# Sheet_1.net
KiCad netlist of a schematic drawn in Altium Designer
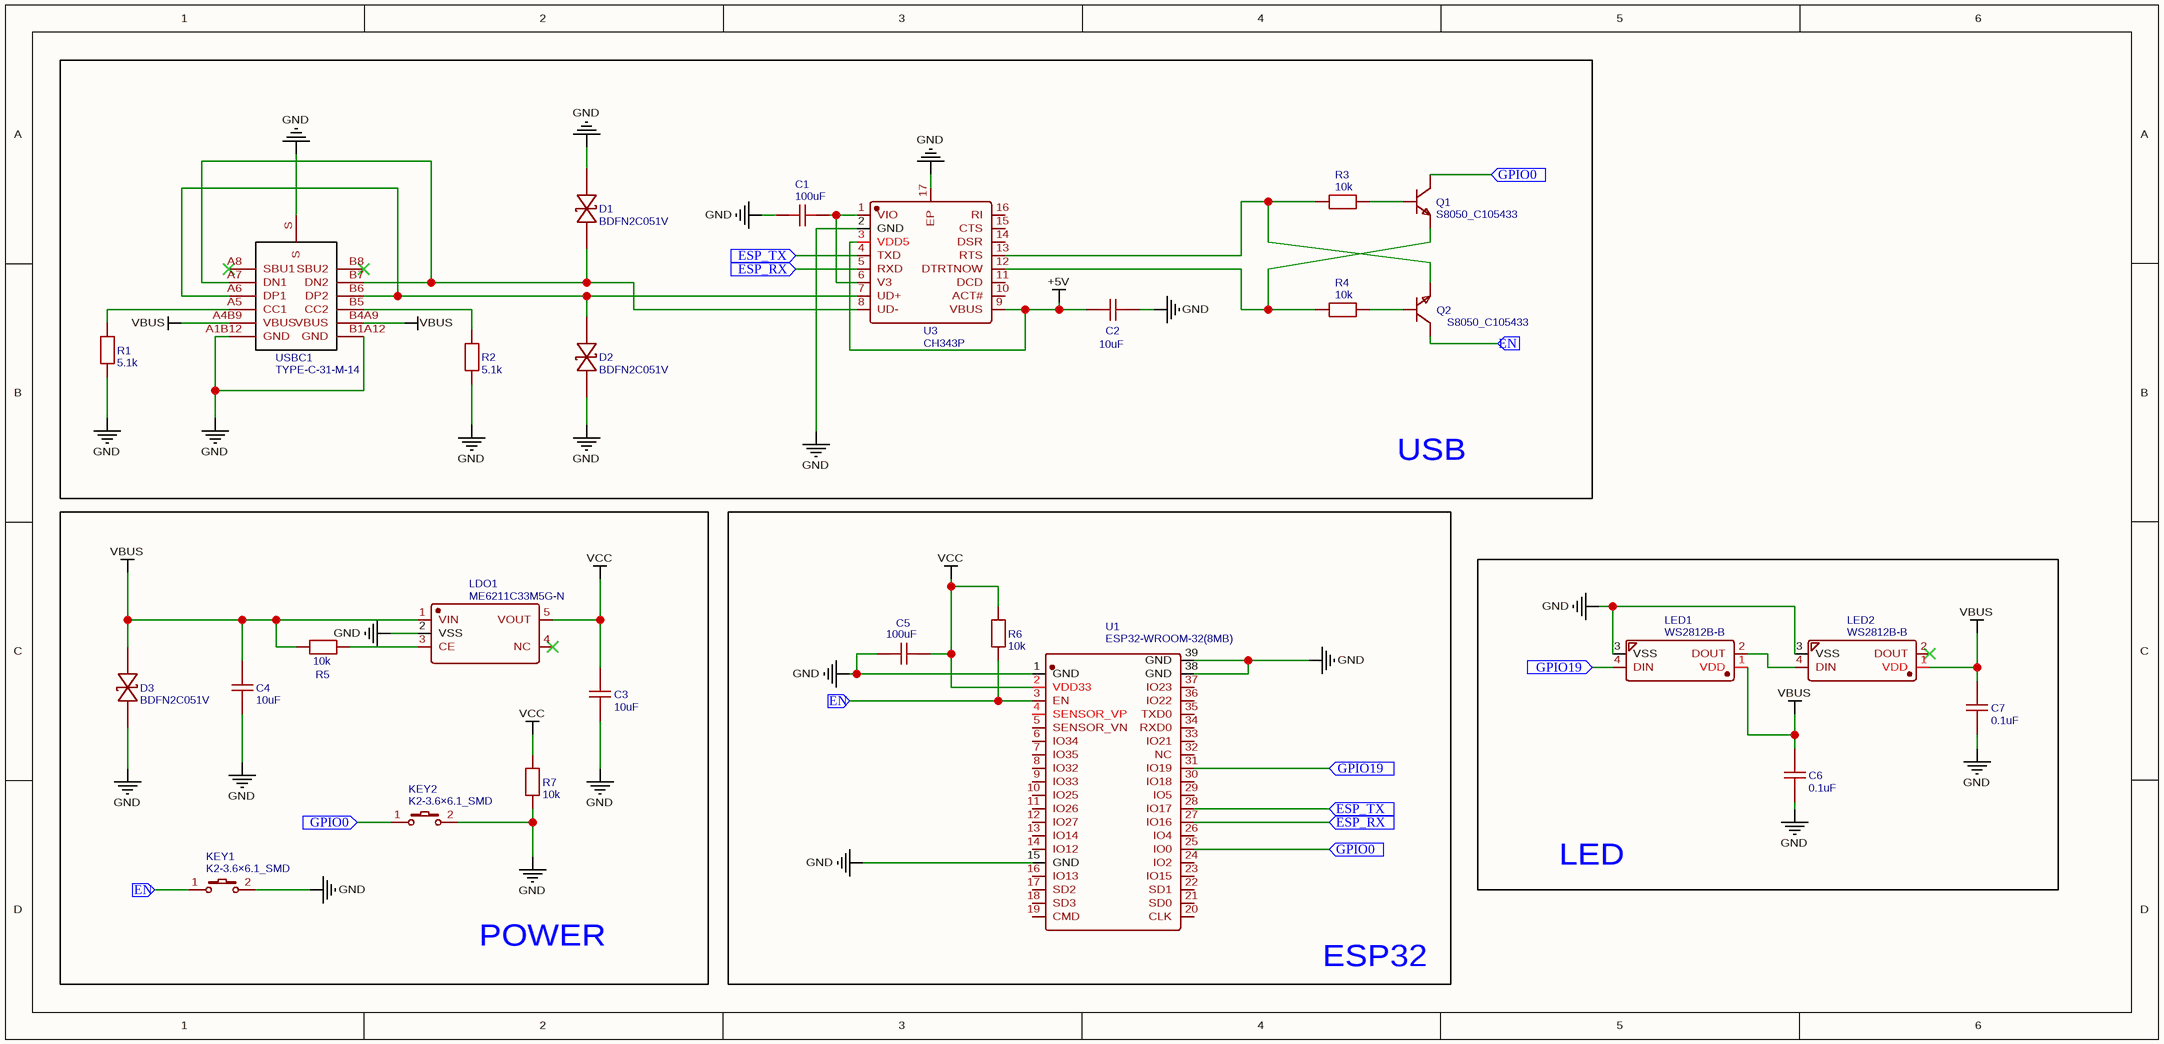
[diagram p0: Sheet_1.schdoc]

(export (version "E")
  (design (tool "Eeschema 10.0.6"))
  (components
    (comp (ref "C1")
      (value "100uF")
      (fields (field (name "CONTRIBUTOR") "LCEDA_Lib"))
      (libsource (lib "altium-import") (part "root_0_100uF_"))
    )
    (comp (ref "C2")
      (value "10uF")
      (fields (field (name "CONTRIBUTOR") "LCEDA_Lib"))
      (libsource (lib "altium-import") (part "root_0_10uF_"))
    )
    (comp (ref "C3")
      (value "10uF")
      (fields (field (name "CONTRIBUTOR") "LCEDA_Lib"))
      (libsource (lib "altium-import") (part "root_1_10uF_"))
    )
    (comp (ref "C4")
      (value "10uF")
      (fields (field (name "CONTRIBUTOR") "LCEDA_Lib"))
      (libsource (lib "altium-import") (part "root_1_10uF_"))
    )
    (comp (ref "C5")
      (value "100uF")
      (fields (field (name "CONTRIBUTOR") "LCEDA_Lib"))
      (libsource (lib "altium-import") (part "root_0_100uF_"))
    )
    (comp (ref "C6")
      (value "0.1uF")
      (fields (field (name "CONTRIBUTOR") "LCEDA_Lib"))
      (libsource (lib "altium-import") (part "root_3_0.1uF_"))
    )
    (comp (ref "C7")
      (value "0.1uF")
      (fields (field (name "CONTRIBUTOR") "LCEDA_Lib"))
      (libsource (lib "altium-import") (part "root_3_0.1uF_"))
    )
    (comp (ref "D1")
      (value "BDFN2C051V")
      (fields (field (name "BOM_SUPPLIER PART") "C152024") (field (name "CONTRIBUTOR") "LCSC"))
      (libsource (lib "altium-import") (part "root_3_BDFN2C051V_"))
    )
    (comp (ref "D2")
      (value "BDFN2C051V")
      (fields (field (name "BOM_SUPPLIER PART") "C152024") (field (name "CONTRIBUTOR") "LCSC"))
      (libsource (lib "altium-import") (part "root_3_BDFN2C051V_"))
    )
    (comp (ref "D3")
      (value "BDFN2C051V")
      (fields (field (name "BOM_SUPPLIER PART") "C152024") (field (name "CONTRIBUTOR") "LCSC"))
      (libsource (lib "altium-import") (part "root_3_BDFN2C051V_"))
    )
    (comp (ref "KEY1")
      (value "K2-3.6×6.1_SMD")
      (fields
        (field (name "BOM_SUPPLIER PART") "C118141")
        (field (name "BOM_MANUFACTURER PART") "K2-1107ST-A4SW-06")
        (field (name "CONTRIBUTOR") "LCEDA_Lib")
      )
      (libsource (lib "altium-import") (part "root_0_K2-3.6×6.1_SMD_"))
    )
    (comp (ref "KEY2")
      (value "K2-3.6×6.1_SMD")
      (fields
        (field (name "BOM_SUPPLIER PART") "C118141")
        (field (name "BOM_MANUFACTURER PART") "K2-1107ST-A4SW-06")
        (field (name "CONTRIBUTOR") "LCEDA_Lib")
      )
      (libsource (lib "altium-import") (part "root_0_K2-3.6×6.1_SMD_"))
    )
    (comp (ref "LDO1")
      (value "ME6211C33M5G-N")
      (fields (field (name "BOM_SUPPLIER PART") "C82942"))
      (libsource (lib "altium-import") (part "root_0_ME6211C33M5G-N_"))
    )
    (comp (ref "LED1")
      (value "WS2812B-B")
      (fields (field (name "BOM_SUPPLIER PART") "C114586") (field (name "CONTRIBUTOR") "LCSC"))
      (libsource (lib "altium-import") (part "root_2_WS2812B-B_"))
    )
    (comp (ref "LED2")
      (value "WS2812B-B")
      (fields (field (name "BOM_SUPPLIER PART") "C114586") (field (name "CONTRIBUTOR") "LCSC"))
      (libsource (lib "altium-import") (part "root_2_WS2812B-B_"))
    )
    (comp (ref "Q1")
      (value "S8050_C105433")
      (fields (field (name "BOM_MANUFACTURER PART") "S8050") (field (name "BOM_SUPPLIER PART") "C105433"))
      (libsource (lib "altium-import") (part "root_0_S8050_C105433_"))
    )
    (comp (ref "Q2")
      (value "S8050_C105433")
      (fields (field (name "BOM_MANUFACTURER PART") "S8050") (field (name "BOM_SUPPLIER PART") "C105433"))
      (libsource (lib "altium-import") (part "root_2_S8050_C105433_"))
    )
    (comp (ref "R1")
      (value "5.1k")
      (fields (field (name "CONTRIBUTOR") "LCEDA_Lib"))
      (libsource (lib "altium-import") (part "root_3_5.1k_"))
    )
    (comp (ref "R2")
      (value "5.1k")
      (fields (field (name "CONTRIBUTOR") "LCEDA_Lib"))
      (libsource (lib "altium-import") (part "root_3_5.1k_"))
    )
    (comp (ref "R3")
      (value "10k")
      (fields (field (name "CONTRIBUTOR") "LCEDA_Lib"))
      (libsource (lib "altium-import") (part "root_0_10k_"))
    )
    (comp (ref "R4")
      (value "10k")
      (fields (field (name "CONTRIBUTOR") "LCEDA_Lib"))
      (libsource (lib "altium-import") (part "root_0_10k_"))
    )
    (comp (ref "R5")
      (value "10k")
      (fields (field (name "CONTRIBUTOR") "LCEDA_Lib"))
      (libsource (lib "altium-import") (part "root_0_10k_"))
    )
    (comp (ref "R6")
      (value "10k")
      (fields (field (name "CONTRIBUTOR") "LCEDA_Lib"))
      (libsource (lib "altium-import") (part "root_1_10k_"))
    )
    (comp (ref "R7")
      (value "10k")
      (fields (field (name "CONTRIBUTOR") "LCEDA_Lib"))
      (libsource (lib "altium-import") (part "root_1_10k_"))
    )
    (comp (ref "U1")
      (value "ESP32-WROOM-32(8MB)")
      (fields
        (field (name "BOM_SUPPLIER PART") "C529582")
        (field (name "BOM_MANUFACTURER PART") "ESP32-WROOM-32-N8")
        (field (name "CONTRIBUTOR") "LCSC")
      )
      (libsource (lib "altium-import") (part "root_0_ESP32-WROOM-32(8MB)_"))
    )
    (comp (ref "U3")
      (value "CH343P")
      (fields (field (name "BOM_SUPPLIER PART") "C2846043") (field (name "CONTRIBUTOR") "LCSC"))
      (libsource (lib "altium-import") (part "root_0_CH343P_"))
    )
    (comp (ref "USBC1")
      (value "TYPE-C-31-M-14")
      (fields (field (name "BOM_SUPPLIER PART") "C223907") (field (name "CONTRIBUTOR") "LCSC"))
      (libsource (lib "altium-import") (part "root_1_TYPE-C-31-M-14_"))
    )
  )
  (nets
    (net (code "1") (name "+5V") (class "Default")
      (node (ref "C2") (pin "1") (pinfunction "1_1") (pintype "passive"))
      (node (ref "U3") (pin "3") (pinfunction "VDD5_3") (pintype "passive"))
      (node (ref "U3") (pin "9") (pinfunction "VBUS_9") (pintype "passive"))
    )
    (net (code "2") (name "/EN") (class "Default")
      (node (ref "KEY1") (pin "1") (pinfunction "1_1") (pintype "passive"))
      (node (ref "Q2") (pin "3") (pinfunction "3_3") (pintype "passive"))
      (node (ref "R6") (pin "1") (pinfunction "1_1") (pintype "passive"))
      (node (ref "U1") (pin "3") (pinfunction "EN_3") (pintype "passive"))
    )
    (net (code "3") (name "/ESP_RX") (class "Default")
      (node (ref "U1") (pin "27") (pinfunction "IO16_27") (pintype "passive"))
      (node (ref "U3") (pin "5") (pinfunction "RXD_5") (pintype "passive"))
    )
    (net (code "4") (name "/ESP_TX") (class "Default")
      (node (ref "U1") (pin "28") (pinfunction "IO17_28") (pintype "passive"))
      (node (ref "U3") (pin "4") (pinfunction "TXD_4") (pintype "passive"))
    )
    (net (code "5") (name "/GPIO0") (class "Default")
      (node (ref "KEY2") (pin "1") (pinfunction "1_1") (pintype "passive"))
      (node (ref "Q1") (pin "3") (pinfunction "3_3") (pintype "passive"))
      (node (ref "U1") (pin "25") (pinfunction "IO0_25") (pintype "passive"))
    )
    (net (code "6") (name "/GPIO19") (class "Default")
      (node (ref "LED1") (pin "4") (pinfunction "DIN_4") (pintype "passive"))
      (node (ref "U1") (pin "31") (pinfunction "IO19_31") (pintype "passive"))
    )
    (net (code "7") (name "GND") (class "Default")
      (node (ref "C1") (pin "1") (pinfunction "1_1") (pintype "passive"))
      (node (ref "C2") (pin "2") (pinfunction "2_2") (pintype "passive"))
      (node (ref "C3") (pin "1") (pinfunction "1_1") (pintype "passive"))
      (node (ref "C4") (pin "1") (pinfunction "1_1") (pintype "passive"))
      (node (ref "C5") (pin "1") (pinfunction "1_1") (pintype "passive"))
      (node (ref "C6") (pin "2") (pinfunction "2_2") (pintype "passive"))
      (node (ref "C7") (pin "2") (pinfunction "2_2") (pintype "passive"))
      (node (ref "D1") (pin "1") (pinfunction "1_1") (pintype "passive"))
      (node (ref "D2") (pin "2") (pinfunction "2_2") (pintype "passive"))
      (node (ref "D3") (pin "2") (pinfunction "2_2") (pintype "passive"))
      (node (ref "KEY1") (pin "2") (pinfunction "2_2") (pintype "passive"))
      (node (ref "KEY2") (pin "2") (pinfunction "2_2") (pintype "passive"))
      (node (ref "LDO1") (pin "2") (pinfunction "VSS_2") (pintype "passive"))
      (node (ref "LED1") (pin "3") (pinfunction "VSS_3") (pintype "passive"))
      (node (ref "LED2") (pin "3") (pinfunction "VSS_3") (pintype "passive"))
      (node (ref "R1") (pin "2") (pinfunction "2_2") (pintype "passive"))
      (node (ref "R2") (pin "2") (pinfunction "2_2") (pintype "passive"))
      (node (ref "R7") (pin "1") (pinfunction "1_1") (pintype "passive"))
      (node (ref "U1") (pin "1") (pinfunction "GND_1") (pintype "passive"))
      (node (ref "U1") (pin "15") (pinfunction "GND_15") (pintype "passive"))
      (node (ref "U1") (pin "38") (pinfunction "GND_38") (pintype "passive"))
      (node (ref "U1") (pin "39") (pinfunction "GND_39") (pintype "passive"))
      (node (ref "U3") (pin "17") (pinfunction "EP_17") (pintype "passive"))
      (node (ref "U3") (pin "2") (pinfunction "GND_2") (pintype "passive"))
      (node (ref "USBC1") (pin "A1B12") (pinfunction "GND_A1B12") (pintype "passive"))
      (node (ref "USBC1") (pin "B1A12") (pinfunction "GND_B1A12") (pintype "passive"))
      (node (ref "USBC1") (pin "S") (pinfunction "S_S") (pintype "passive"))
    )
    (net (code "8") (name "Net-(LDO1-CE)") (class "Default")
      (node (ref "LDO1") (pin "3") (pinfunction "CE_3") (pintype "passive"))
      (node (ref "R5") (pin "2") (pinfunction "2_2") (pintype "passive"))
    )
    (net (code "9") (name "Net-(LED1-DOUT)") (class "Default")
      (node (ref "LED1") (pin "2") (pinfunction "DOUT_2") (pintype "passive"))
      (node (ref "LED2") (pin "4") (pinfunction "DIN_4") (pintype "passive"))
    )
    (net (code "10") (name "Net-(Q1-Pad1)") (class "Default")
      (node (ref "Q1") (pin "1") (pinfunction "1_1") (pintype "passive"))
      (node (ref "R3") (pin "2") (pinfunction "2_2") (pintype "passive"))
    )
    (net (code "11") (name "Net-(Q2-Pad1)") (class "Default")
      (node (ref "Q2") (pin "1") (pinfunction "1_1") (pintype "passive"))
      (node (ref "R4") (pin "2") (pinfunction "2_2") (pintype "passive"))
    )
    (net (code "12") (name "Net-(U3-DTRTNOW)") (class "Default")
      (node (ref "Q1") (pin "2") (pinfunction "2_2") (pintype "passive"))
      (node (ref "R4") (pin "1") (pinfunction "1_1") (pintype "passive"))
      (node (ref "U3") (pin "12") (pinfunction "DTRTNOW_12") (pintype "passive"))
    )
    (net (code "13") (name "Net-(U3-RTS)") (class "Default")
      (node (ref "Q2") (pin "2") (pinfunction "2_2") (pintype "passive"))
      (node (ref "R3") (pin "1") (pinfunction "1_1") (pintype "passive"))
      (node (ref "U3") (pin "13") (pinfunction "RTS_13") (pintype "passive"))
    )
    (net (code "14") (name "Net-(U3-UD+)") (class "Default")
      (node (ref "D2") (pin "1") (pinfunction "1_1") (pintype "passive"))
      (node (ref "U3") (pin "7") (pinfunction "UD+_7") (pintype "passive"))
      (node (ref "USBC1") (pin "A6") (pinfunction "DP1_A6") (pintype "passive"))
      (node (ref "USBC1") (pin "B6") (pinfunction "DP2_B6") (pintype "passive"))
    )
    (net (code "15") (name "Net-(U3-UD-)") (class "Default")
      (node (ref "D1") (pin "2") (pinfunction "2_2") (pintype "passive"))
      (node (ref "U3") (pin "8") (pinfunction "UD-_8") (pintype "passive"))
      (node (ref "USBC1") (pin "A7") (pinfunction "DN1_A7") (pintype "passive"))
      (node (ref "USBC1") (pin "B7") (pinfunction "DN2_B7") (pintype "passive"))
    )
    (net (code "16") (name "Net-(U3-V3)") (class "Default")
      (node (ref "C1") (pin "2") (pinfunction "2_2") (pintype "passive"))
      (node (ref "U3") (pin "1") (pinfunction "VIO_1") (pintype "passive"))
      (node (ref "U3") (pin "6") (pinfunction "V3_6") (pintype "passive"))
    )
    (net (code "17") (name "Net-(USBC1-CC1)") (class "Default")
      (node (ref "R1") (pin "1") (pinfunction "1_1") (pintype "passive"))
      (node (ref "USBC1") (pin "A5") (pinfunction "CC1_A5") (pintype "passive"))
    )
    (net (code "18") (name "Net-(USBC1-CC2)") (class "Default")
      (node (ref "R2") (pin "1") (pinfunction "1_1") (pintype "passive"))
      (node (ref "USBC1") (pin "B5") (pinfunction "CC2_B5") (pintype "passive"))
    )
    (net (code "19") (name "VBUS") (class "Default")
      (node (ref "C4") (pin "2") (pinfunction "2_2") (pintype "passive"))
      (node (ref "C6") (pin "1") (pinfunction "1_1") (pintype "passive"))
      (node (ref "C7") (pin "1") (pinfunction "1_1") (pintype "passive"))
      (node (ref "D3") (pin "1") (pinfunction "1_1") (pintype "passive"))
      (node (ref "LDO1") (pin "1") (pinfunction "VIN_1") (pintype "passive"))
      (node (ref "LED1") (pin "1") (pinfunction "VDD_1") (pintype "passive"))
      (node (ref "LED2") (pin "1") (pinfunction "VDD_1") (pintype "passive"))
      (node (ref "R5") (pin "1") (pinfunction "1_1") (pintype "passive"))
      (node (ref "USBC1") (pin "A4B9") (pinfunction "VBUS_A4B9") (pintype "passive"))
      (node (ref "USBC1") (pin "B4A9") (pinfunction "VBUS_B4A9") (pintype "passive"))
    )
    (net (code "20") (name "VCC") (class "Default")
      (node (ref "C3") (pin "2") (pinfunction "2_2") (pintype "passive"))
      (node (ref "C5") (pin "2") (pinfunction "2_2") (pintype "passive"))
      (node (ref "LDO1") (pin "5") (pinfunction "VOUT_5") (pintype "passive"))
      (node (ref "R6") (pin "2") (pinfunction "2_2") (pintype "passive"))
      (node (ref "R7") (pin "2") (pinfunction "2_2") (pintype "passive"))
      (node (ref "U1") (pin "2") (pinfunction "VDD33_2") (pintype "passive"))
    )
    (net (code "21") (name "unconnected-(LDO1-NC-Pad4)") (class "Default")
      (node (ref "LDO1") (pin "4") (pinfunction "NC_4") (pintype "passive+no_connect"))
    )
    (net (code "22") (name "unconnected-(LED2-DOUT-Pad2)") (class "Default")
      (node (ref "LED2") (pin "2") (pinfunction "DOUT_2") (pintype "passive+no_connect"))
    )
    (net (code "23") (name "unconnected-(U1-CLK-Pad20)") (class "Default")
      (node (ref "U1") (pin "20") (pinfunction "CLK_20") (pintype "passive"))
    )
    (net (code "24") (name "unconnected-(U1-CMD-Pad19)") (class "Default")
      (node (ref "U1") (pin "19") (pinfunction "CMD_19") (pintype "passive"))
    )
    (net (code "25") (name "unconnected-(U1-IO2-Pad24)") (class "Default")
      (node (ref "U1") (pin "24") (pinfunction "IO2_24") (pintype "passive"))
    )
    (net (code "26") (name "unconnected-(U1-IO4-Pad26)") (class "Default")
      (node (ref "U1") (pin "26") (pinfunction "IO4_26") (pintype "passive"))
    )
    (net (code "27") (name "unconnected-(U1-IO5-Pad29)") (class "Default")
      (node (ref "U1") (pin "29") (pinfunction "IO5_29") (pintype "passive"))
    )
    (net (code "28") (name "unconnected-(U1-IO12-Pad14)") (class "Default")
      (node (ref "U1") (pin "14") (pinfunction "IO12_14") (pintype "passive"))
    )
    (net (code "29") (name "unconnected-(U1-IO13-Pad16)") (class "Default")
      (node (ref "U1") (pin "16") (pinfunction "IO13_16") (pintype "passive"))
    )
    (net (code "30") (name "unconnected-(U1-IO14-Pad13)") (class "Default")
      (node (ref "U1") (pin "13") (pinfunction "IO14_13") (pintype "passive"))
    )
    (net (code "31") (name "unconnected-(U1-IO15-Pad23)") (class "Default")
      (node (ref "U1") (pin "23") (pinfunction "IO15_23") (pintype "passive"))
    )
    (net (code "32") (name "unconnected-(U1-IO18-Pad30)") (class "Default")
      (node (ref "U1") (pin "30") (pinfunction "IO18_30") (pintype "passive"))
    )
    (net (code "33") (name "unconnected-(U1-IO21-Pad33)") (class "Default")
      (node (ref "U1") (pin "33") (pinfunction "IO21_33") (pintype "passive"))
    )
    (net (code "34") (name "unconnected-(U1-IO22-Pad36)") (class "Default")
      (node (ref "U1") (pin "36") (pinfunction "IO22_36") (pintype "passive"))
    )
    (net (code "35") (name "unconnected-(U1-IO23-Pad37)") (class "Default")
      (node (ref "U1") (pin "37") (pinfunction "IO23_37") (pintype "passive"))
    )
    (net (code "36") (name "unconnected-(U1-IO25-Pad10)") (class "Default")
      (node (ref "U1") (pin "10") (pinfunction "IO25_10") (pintype "passive"))
    )
    (net (code "37") (name "unconnected-(U1-IO26-Pad11)") (class "Default")
      (node (ref "U1") (pin "11") (pinfunction "IO26_11") (pintype "passive"))
    )
    (net (code "38") (name "unconnected-(U1-IO27-Pad12)") (class "Default")
      (node (ref "U1") (pin "12") (pinfunction "IO27_12") (pintype "passive"))
    )
    (net (code "39") (name "unconnected-(U1-IO32-Pad8)") (class "Default")
      (node (ref "U1") (pin "8") (pinfunction "IO32_8") (pintype "passive"))
    )
    (net (code "40") (name "unconnected-(U1-IO33-Pad9)") (class "Default")
      (node (ref "U1") (pin "9") (pinfunction "IO33_9") (pintype "passive"))
    )
    (net (code "41") (name "unconnected-(U1-IO34-Pad6)") (class "Default")
      (node (ref "U1") (pin "6") (pinfunction "IO34_6") (pintype "passive"))
    )
    (net (code "42") (name "unconnected-(U1-IO35-Pad7)") (class "Default")
      (node (ref "U1") (pin "7") (pinfunction "IO35_7") (pintype "passive"))
    )
    (net (code "43") (name "unconnected-(U1-NC-Pad32)") (class "Default")
      (node (ref "U1") (pin "32") (pinfunction "NC_32") (pintype "passive"))
    )
    (net (code "44") (name "unconnected-(U1-RXD0-Pad34)") (class "Default")
      (node (ref "U1") (pin "34") (pinfunction "RXD0_34") (pintype "passive"))
    )
    (net (code "45") (name "unconnected-(U1-SD0-Pad21)") (class "Default")
      (node (ref "U1") (pin "21") (pinfunction "SD0_21") (pintype "passive"))
    )
    (net (code "46") (name "unconnected-(U1-SD1-Pad22)") (class "Default")
      (node (ref "U1") (pin "22") (pinfunction "SD1_22") (pintype "passive"))
    )
    (net (code "47") (name "unconnected-(U1-SD2-Pad17)") (class "Default")
      (node (ref "U1") (pin "17") (pinfunction "SD2_17") (pintype "passive"))
    )
    (net (code "48") (name "unconnected-(U1-SD3-Pad18)") (class "Default")
      (node (ref "U1") (pin "18") (pinfunction "SD3_18") (pintype "passive"))
    )
    (net (code "49") (name "unconnected-(U1-SENSOR_VN-Pad5)") (class "Default")
      (node (ref "U1") (pin "5") (pinfunction "SENSOR_VN_5") (pintype "passive"))
    )
    (net (code "50") (name "unconnected-(U1-SENSOR_VP-Pad4)") (class "Default")
      (node (ref "U1") (pin "4") (pinfunction "SENSOR_VP_4") (pintype "passive"))
    )
    (net (code "51") (name "unconnected-(U1-TXD0-Pad35)") (class "Default")
      (node (ref "U1") (pin "35") (pinfunction "TXD0_35") (pintype "passive"))
    )
    (net (code "52") (name "unconnected-(U3-ACT#-Pad10)") (class "Default")
      (node (ref "U3") (pin "10") (pinfunction "ACT#_10") (pintype "passive"))
    )
    (net (code "53") (name "unconnected-(U3-CTS-Pad15)") (class "Default")
      (node (ref "U3") (pin "15") (pinfunction "CTS_15") (pintype "passive"))
    )
    (net (code "54") (name "unconnected-(U3-DCD-Pad11)") (class "Default")
      (node (ref "U3") (pin "11") (pinfunction "DCD_11") (pintype "passive"))
    )
    (net (code "55") (name "unconnected-(U3-DSR-Pad14)") (class "Default")
      (node (ref "U3") (pin "14") (pinfunction "DSR_14") (pintype "passive"))
    )
    (net (code "56") (name "unconnected-(U3-RI-Pad16)") (class "Default")
      (node (ref "U3") (pin "16") (pinfunction "RI_16") (pintype "passive"))
    )
    (net (code "57") (name "unconnected-(USBC1-SBU1-PadA8)") (class "Default")
      (node (ref "USBC1") (pin "A8") (pinfunction "SBU1_A8") (pintype "passive+no_connect"))
    )
    (net (code "58") (name "unconnected-(USBC1-SBU2-PadB8)") (class "Default")
      (node (ref "USBC1") (pin "B8") (pinfunction "SBU2_B8") (pintype "passive+no_connect"))
    )
  )
)
